# cheetah_driver_2.net
KiCad netlist of a schematic drawn in EAGLE
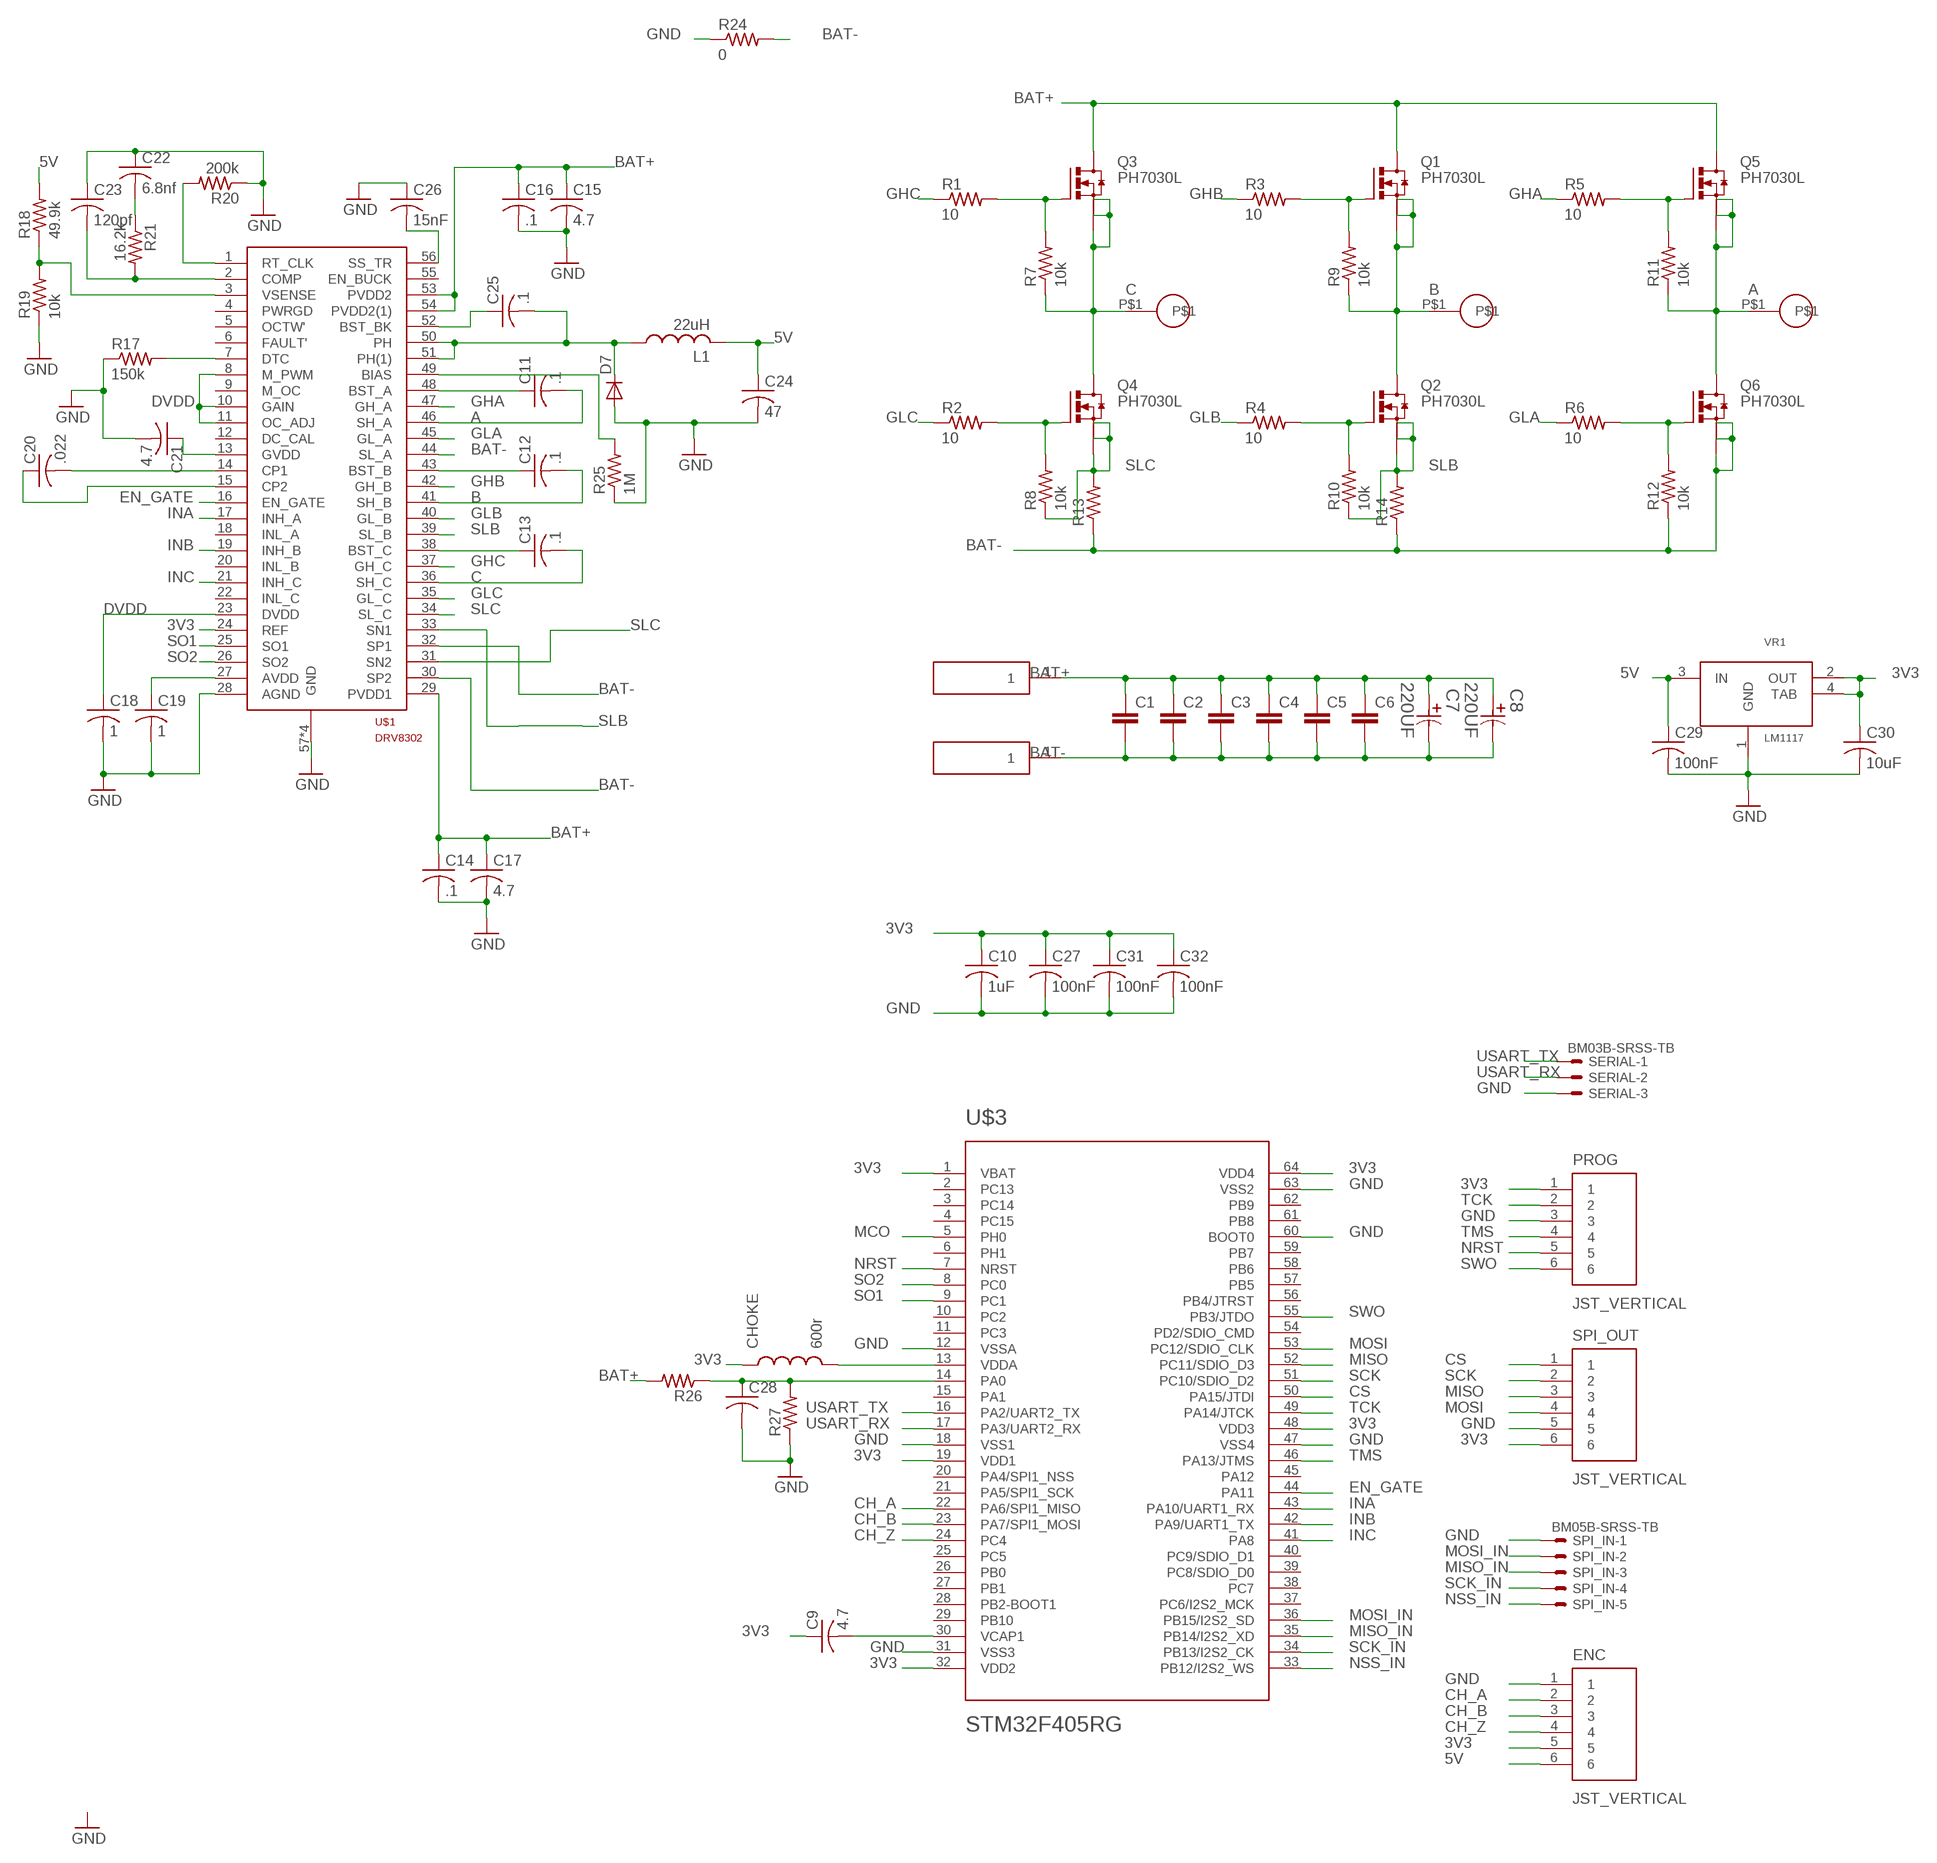
[diagram p0: schematic, sheet 1]

(export (version "E")
  (design (tool "Eeschema 10.0.6"))
  (components
    (comp (ref "C1")
      (value "C-EUC0805")
      (footprint "eagle-import:C0805")
      (libsource (lib "eagle-import") (part "C-EUC0805"))
    )
    (comp (ref "C2")
      (value "C-EUC0805")
      (footprint "eagle-import:C0805")
      (libsource (lib "eagle-import") (part "C-EUC0805"))
    )
    (comp (ref "C3")
      (value "C-EUC0805")
      (footprint "eagle-import:C0805")
      (libsource (lib "eagle-import") (part "C-EUC0805"))
    )
    (comp (ref "C4")
      (value "C-EUC0805")
      (footprint "eagle-import:C0805")
      (libsource (lib "eagle-import") (part "C-EUC0805"))
    )
    (comp (ref "C5")
      (value "C-EUC0805")
      (footprint "eagle-import:C0805")
      (libsource (lib "eagle-import") (part "C-EUC0805"))
    )
    (comp (ref "C6")
      (value "C-EUC0805")
      (footprint "eagle-import:C0805")
      (libsource (lib "eagle-import") (part "C-EUC0805"))
    )
    (comp (ref "C7")
      (value "220UF")
      (footprint "eagle-import:CAPAE830X1050N")
      (fields (field (name "MPN") "EEE-TK1A221P") (field (name "TOLERANCE") "±20 %"))
      (libsource (lib "eagle-import") (part "EEE--CASE-FTK1A221P"))
    )
    (comp (ref "C8")
      (value "220UF")
      (footprint "eagle-import:CAPAE830X1050N")
      (fields (field (name "MPN") "EEE-TK1A221P") (field (name "TOLERANCE") "±20 %"))
      (libsource (lib "eagle-import") (part "EEE--CASE-FTK1A221P"))
    )
    (comp (ref "C9")
      (value "4.7")
      (footprint "eagle-import:C0603")
      (libsource (lib "eagle-import") (part "C-USC0603"))
    )
    (comp (ref "C10")
      (value "1uF")
      (footprint "eagle-import:C0603")
      (libsource (lib "eagle-import") (part "C-USC0603"))
    )
    (comp (ref "C11")
      (value ".1")
      (footprint "eagle-import:C0603")
      (libsource (lib "eagle-import") (part "C-USC0603"))
    )
    (comp (ref "C12")
      (value ".1")
      (footprint "eagle-import:C0603")
      (libsource (lib "eagle-import") (part "C-USC0603"))
    )
    (comp (ref "C13")
      (value ".1")
      (footprint "eagle-import:C0603")
      (libsource (lib "eagle-import") (part "C-USC0603"))
    )
    (comp (ref "C14")
      (value ".1")
      (footprint "eagle-import:C0603")
      (libsource (lib "eagle-import") (part "C-USC0603"))
    )
    (comp (ref "C15")
      (value "4.7")
      (footprint "eagle-import:C0805")
      (libsource (lib "eagle-import") (part "C-USC0805"))
    )
    (comp (ref "C16")
      (value ".1")
      (footprint "eagle-import:C0603")
      (libsource (lib "eagle-import") (part "C-USC0603"))
    )
    (comp (ref "C17")
      (value "4.7")
      (footprint "eagle-import:C0805")
      (libsource (lib "eagle-import") (part "C-USC0805"))
    )
    (comp (ref "C18")
      (value "1")
      (footprint "eagle-import:C0603")
      (libsource (lib "eagle-import") (part "C-USC0603"))
    )
    (comp (ref "C19")
      (value "1")
      (footprint "eagle-import:C0603")
      (libsource (lib "eagle-import") (part "C-USC0603"))
    )
    (comp (ref "C20")
      (value ".022")
      (footprint "eagle-import:C0603")
      (libsource (lib "eagle-import") (part "C-USC0603"))
    )
    (comp (ref "C21")
      (value "4.7")
      (footprint "eagle-import:C0805")
      (libsource (lib "eagle-import") (part "C-USC0805"))
    )
    (comp (ref "C22")
      (value "6.8nf")
      (footprint "eagle-import:C0603")
      (libsource (lib "eagle-import") (part "C-USC0603"))
    )
    (comp (ref "C23")
      (value "120pf")
      (footprint "eagle-import:C0603")
      (libsource (lib "eagle-import") (part "C-USC0603"))
    )
    (comp (ref "C24")
      (value "47")
      (footprint "eagle-import:C1210")
      (libsource (lib "eagle-import") (part "C-USC1210"))
    )
    (comp (ref "C25")
      (value ".1")
      (footprint "eagle-import:C0603")
      (libsource (lib "eagle-import") (part "C-USC0603"))
    )
    (comp (ref "C26")
      (value "15nF")
      (footprint "eagle-import:C0603")
      (libsource (lib "eagle-import") (part "C-USC0603"))
    )
    (comp (ref "C27")
      (value "100nF")
      (footprint "eagle-import:C0603")
      (libsource (lib "eagle-import") (part "C-USC0603"))
    )
    (comp (ref "C28")
      (value "C-USC0603")
      (footprint "eagle-import:C0603")
      (libsource (lib "eagle-import") (part "C-USC0603"))
    )
    (comp (ref "C29")
      (value "100nF")
      (footprint "eagle-import:C0603")
      (libsource (lib "eagle-import") (part "C-USC0603"))
    )
    (comp (ref "C30")
      (value "10uF")
      (footprint "eagle-import:C0603")
      (libsource (lib "eagle-import") (part "C-USC0603"))
    )
    (comp (ref "C31")
      (value "100nF")
      (footprint "eagle-import:C0603")
      (libsource (lib "eagle-import") (part "C-USC0603"))
    )
    (comp (ref "C32")
      (value "100nF")
      (footprint "eagle-import:C0603")
      (libsource (lib "eagle-import") (part "C-USC0603"))
    )
    (comp (ref "CHOKE")
      (value "600r")
      (footprint "eagle-import:0603")
      (libsource (lib "eagle-import") (part "INDUCTOR0603"))
    )
    (comp (ref "D7")
      (value "DIODE-DO-214AC")
      (footprint "eagle-import:DO-214AC")
      (libsource (lib "eagle-import") (part "DIODE-DO-214AC"))
    )
    (comp (ref "ENC")
      (value "JST_VERTICAL")
      (footprint "eagle-import:JST-6-SMD-VERT-1.0MM")
      (libsource (lib "eagle-import") (part "JST_VERTICAL"))
    )
    (comp (ref "J4")
      (value "0.125_PAD")
      (footprint "eagle-import:0.125_PAD")
      (libsource (lib "eagle-import") (part "0.125_PAD"))
    )
    (comp (ref "J5")
      (value "0.125_PAD")
      (footprint "eagle-import:0.125_PAD")
      (libsource (lib "eagle-import") (part "0.125_PAD"))
    )
    (comp (ref "L1")
      (value "22uH")
      (footprint "eagle-import:L4532P")
      (libsource (lib "eagle-import") (part "L-USL4532P"))
    )
    (comp (ref "PROG")
      (value "JST_VERTICAL")
      (footprint "eagle-import:JST-6-SMD-VERT-1.0MM")
      (libsource (lib "eagle-import") (part "JST_VERTICAL"))
    )
    (comp (ref "Q1")
      (value "PH7030L")
      (footprint "eagle-import:SOT669")
      (libsource (lib "eagle-import") (part "PH7030L"))
    )
    (comp (ref "Q2")
      (value "PH7030L")
      (footprint "eagle-import:SOT669")
      (libsource (lib "eagle-import") (part "PH7030L"))
    )
    (comp (ref "Q3")
      (value "PH7030L")
      (footprint "eagle-import:SOT669")
      (libsource (lib "eagle-import") (part "PH7030L"))
    )
    (comp (ref "Q4")
      (value "PH7030L")
      (footprint "eagle-import:SOT669")
      (libsource (lib "eagle-import") (part "PH7030L"))
    )
    (comp (ref "Q5")
      (value "PH7030L")
      (footprint "eagle-import:SOT669")
      (libsource (lib "eagle-import") (part "PH7030L"))
    )
    (comp (ref "Q6")
      (value "PH7030L")
      (footprint "eagle-import:SOT669")
      (libsource (lib "eagle-import") (part "PH7030L"))
    )
    (comp (ref "R1")
      (value "10")
      (footprint "eagle-import:R0603")
      (libsource (lib "eagle-import") (part "R-US_R0603"))
    )
    (comp (ref "R2")
      (value "10")
      (footprint "eagle-import:R0603")
      (libsource (lib "eagle-import") (part "R-US_R0603"))
    )
    (comp (ref "R3")
      (value "10")
      (footprint "eagle-import:R0603")
      (libsource (lib "eagle-import") (part "R-US_R0603"))
    )
    (comp (ref "R4")
      (value "10")
      (footprint "eagle-import:R0603")
      (libsource (lib "eagle-import") (part "R-US_R0603"))
    )
    (comp (ref "R5")
      (value "10")
      (footprint "eagle-import:R0603")
      (libsource (lib "eagle-import") (part "R-US_R0603"))
    )
    (comp (ref "R6")
      (value "10")
      (footprint "eagle-import:R0603")
      (libsource (lib "eagle-import") (part "R-US_R0603"))
    )
    (comp (ref "R7")
      (value "10k")
      (footprint "eagle-import:R0603")
      (libsource (lib "eagle-import") (part "R-US_R0603"))
    )
    (comp (ref "R8")
      (value "10k")
      (footprint "eagle-import:R0603")
      (libsource (lib "eagle-import") (part "R-US_R0603"))
    )
    (comp (ref "R9")
      (value "10k")
      (footprint "eagle-import:R0603")
      (libsource (lib "eagle-import") (part "R-US_R0603"))
    )
    (comp (ref "R10")
      (value "10k")
      (footprint "eagle-import:R0603")
      (libsource (lib "eagle-import") (part "R-US_R0603"))
    )
    (comp (ref "R11")
      (value "10k")
      (footprint "eagle-import:R0603")
      (libsource (lib "eagle-import") (part "R-US_R0603"))
    )
    (comp (ref "R12")
      (value "10k")
      (footprint "eagle-import:R0603")
      (libsource (lib "eagle-import") (part "R-US_R0603"))
    )
    (comp (ref "R13")
      (value "R-US_R1210")
      (footprint "eagle-import:R1210")
      (libsource (lib "eagle-import") (part "R-US_R1210"))
    )
    (comp (ref "R14")
      (value "R-US_R1210")
      (footprint "eagle-import:R1210")
      (libsource (lib "eagle-import") (part "R-US_R1210"))
    )
    (comp (ref "R17")
      (value "150k")
      (footprint "eagle-import:R0603")
      (libsource (lib "eagle-import") (part "R-US_R0603"))
    )
    (comp (ref "R18")
      (value "49.9k")
      (footprint "eagle-import:R0603")
      (libsource (lib "eagle-import") (part "R-US_R0603"))
    )
    (comp (ref "R19")
      (value "10k")
      (footprint "eagle-import:R0603")
      (libsource (lib "eagle-import") (part "R-US_R0603"))
    )
    (comp (ref "R20")
      (value "200k")
      (footprint "eagle-import:R0603")
      (libsource (lib "eagle-import") (part "R-US_R0603"))
    )
    (comp (ref "R21")
      (value "16.2k")
      (footprint "eagle-import:R0603")
      (libsource (lib "eagle-import") (part "R-US_R0603"))
    )
    (comp (ref "R24")
      (value "0")
      (footprint "eagle-import:R0603")
      (libsource (lib "eagle-import") (part "R-US_R0603"))
    )
    (comp (ref "R25")
      (value "1M")
      (footprint "eagle-import:R0603")
      (libsource (lib "eagle-import") (part "R-US_R0603"))
    )
    (comp (ref "R26")
      (value "R-US_R0603")
      (footprint "eagle-import:R0603")
      (libsource (lib "eagle-import") (part "R-US_R0603"))
    )
    (comp (ref "R27")
      (value "R-US_R0603")
      (footprint "eagle-import:R0603")
      (libsource (lib "eagle-import") (part "R-US_R0603"))
    )
    (comp (ref "SERIAL")
      (value "BM03B-SRSS-TB")
      (footprint "eagle-import:BM03B-SRSS-TB")
      (libsource (lib "eagle-import") (part "?M03B-SRSS-TBB"))
    )
    (comp (ref "SPI_IN")
      (value "BM05B-SRSS-TB")
      (footprint "eagle-import:BM05B-SRSS-TB")
      (libsource (lib "eagle-import") (part "?M05B-SRSS-TBB"))
    )
    (comp (ref "SPI_OUT")
      (value "JST_VERTICAL")
      (footprint "eagle-import:JST-6-SMD-VERT-1.0MM")
      (libsource (lib "eagle-import") (part "JST_VERTICAL"))
    )
    (comp (ref "U$1")
      (value "DRV8302")
      (footprint "eagle-import:HTSSOP56")
      (libsource (lib "eagle-import") (part "DRV8302"))
    )
    (comp (ref "U$2")
      (value "18_AWG_PAD")
      (footprint "eagle-import:18_AWG_PAD")
      (libsource (lib "eagle-import") (part "18_AWG_PAD"))
    )
    (comp (ref "U$3")
      (value "STM32F405RG")
      (footprint "eagle-import:TQFP64")
      (libsource (lib "eagle-import") (part "STM32F405RG"))
    )
    (comp (ref "U$4")
      (value "18_AWG_PAD")
      (footprint "eagle-import:18_AWG_PAD")
      (libsource (lib "eagle-import") (part "18_AWG_PAD"))
    )
    (comp (ref "U$5")
      (value "18_AWG_PAD")
      (footprint "eagle-import:18_AWG_PAD")
      (libsource (lib "eagle-import") (part "18_AWG_PAD"))
    )
    (comp (ref "VR1")
      (value "LM1117")
      (footprint "eagle-import:SOT-223")
      (libsource (lib "eagle-import") (part "LM1117"))
    )
  )
  (nets
    (net (code "1") (name "/3V3") (class "Default")
      (node (ref "C10") (pin "1") (pinfunction "1_1") (pintype "passive"))
      (node (ref "C27") (pin "1") (pinfunction "1_1") (pintype "passive"))
      (node (ref "C30") (pin "1") (pinfunction "1_1") (pintype "passive"))
      (node (ref "C31") (pin "1") (pinfunction "1_1") (pintype "passive"))
      (node (ref "C32") (pin "1") (pinfunction "1_1") (pintype "passive"))
      (node (ref "C9") (pin "1") (pinfunction "1_1") (pintype "passive"))
      (node (ref "CHOKE") (pin "1") (pinfunction "1_1") (pintype "passive"))
      (node (ref "ENC") (pin "5") (pinfunction "5_5") (pintype "bidirectional"))
      (node (ref "PROG") (pin "1") (pinfunction "1_1") (pintype "bidirectional"))
      (node (ref "SPI_OUT") (pin "6") (pinfunction "6_6") (pintype "bidirectional"))
      (node (ref "U$1") (pin "24") (pinfunction "REF_24") (pintype "bidirectional"))
      (node (ref "U$3") (pin "1") (pinfunction "VBAT_1") (pintype "bidirectional"))
      (node (ref "U$3") (pin "19") (pinfunction "VDD1_19") (pintype "bidirectional"))
      (node (ref "U$3") (pin "32") (pinfunction "VDD2_32") (pintype "bidirectional"))
      (node (ref "U$3") (pin "48") (pinfunction "VDD3_48") (pintype "bidirectional"))
      (node (ref "U$3") (pin "64") (pinfunction "VDD4_64") (pintype "bidirectional"))
      (node (ref "VR1") (pin "2") (pinfunction "OUT_2") (pintype "bidirectional"))
      (node (ref "VR1") (pin "4") (pinfunction "TAB_4") (pintype "bidirectional"))
    )
    (net (code "2") (name "/5V") (class "Default")
      (node (ref "C24") (pin "1") (pinfunction "1_1") (pintype "passive"))
      (node (ref "C29") (pin "1") (pinfunction "1_1") (pintype "passive"))
      (node (ref "ENC") (pin "6") (pinfunction "6_6") (pintype "bidirectional"))
      (node (ref "L1") (pin "2") (pinfunction "2_2") (pintype "passive"))
      (node (ref "R18") (pin "2") (pinfunction "2_2") (pintype "passive"))
      (node (ref "VR1") (pin "3") (pinfunction "IN_3") (pintype "bidirectional"))
    )
    (net (code "3") (name "/A") (class "Default")
      (node (ref "C11") (pin "2") (pinfunction "2_2") (pintype "passive"))
      (node (ref "Q5") (pin "1") (pinfunction "S_1") (pintype "passive"))
      (node (ref "Q5") (pin "2") (pinfunction "S_2") (pintype "passive"))
      (node (ref "Q5") (pin "3") (pinfunction "S_3") (pintype "passive"))
      (node (ref "Q6") (pin "MB") (pinfunction "D_MB") (pintype "passive"))
      (node (ref "R11") (pin "1") (pinfunction "1_1") (pintype "passive"))
      (node (ref "U$1") (pin "46") (pinfunction "SH_A_46") (pintype "bidirectional"))
      (node (ref "U$5") (pin "P$1") (pinfunction "P$1_P$1") (pintype "bidirectional"))
    )
    (net (code "4") (name "/B") (class "Default")
      (node (ref "C12") (pin "2") (pinfunction "2_2") (pintype "passive"))
      (node (ref "Q1") (pin "1") (pinfunction "S_1") (pintype "passive"))
      (node (ref "Q1") (pin "2") (pinfunction "S_2") (pintype "passive"))
      (node (ref "Q1") (pin "3") (pinfunction "S_3") (pintype "passive"))
      (node (ref "Q2") (pin "MB") (pinfunction "D_MB") (pintype "passive"))
      (node (ref "R9") (pin "1") (pinfunction "1_1") (pintype "passive"))
      (node (ref "U$1") (pin "41") (pinfunction "SH_B_41") (pintype "bidirectional"))
      (node (ref "U$4") (pin "P$1") (pinfunction "P$1_P$1") (pintype "bidirectional"))
    )
    (net (code "5") (name "/BAT+") (class "Default")
      (node (ref "C1") (pin "1") (pinfunction "1_1") (pintype "passive"))
      (node (ref "C14") (pin "1") (pinfunction "1_1") (pintype "passive"))
      (node (ref "C15") (pin "1") (pinfunction "1_1") (pintype "passive"))
      (node (ref "C16") (pin "1") (pinfunction "1_1") (pintype "passive"))
      (node (ref "C17") (pin "1") (pinfunction "1_1") (pintype "passive"))
      (node (ref "C2") (pin "1") (pinfunction "1_1") (pintype "passive"))
      (node (ref "C3") (pin "1") (pinfunction "1_1") (pintype "passive"))
      (node (ref "C4") (pin "1") (pinfunction "1_1") (pintype "passive"))
      (node (ref "C5") (pin "1") (pinfunction "1_1") (pintype "passive"))
      (node (ref "C6") (pin "1") (pinfunction "1_1") (pintype "passive"))
      (node (ref "C7") (pin "1") (pinfunction "1_1") (pintype "passive"))
      (node (ref "C8") (pin "1") (pinfunction "1_1") (pintype "passive"))
      (node (ref "J4") (pin "1") (pinfunction "1_1") (pintype "bidirectional"))
      (node (ref "Q1") (pin "MB") (pinfunction "D_MB") (pintype "passive"))
      (node (ref "Q3") (pin "MB") (pinfunction "D_MB") (pintype "passive"))
      (node (ref "Q5") (pin "MB") (pinfunction "D_MB") (pintype "passive"))
      (node (ref "R26") (pin "2") (pinfunction "2_2") (pintype "passive"))
      (node (ref "U$1") (pin "29") (pinfunction "PVDD1_29") (pintype "bidirectional"))
      (node (ref "U$1") (pin "53") (pinfunction "PVDD2_53") (pintype "bidirectional"))
      (node (ref "U$1") (pin "54") (pinfunction "PVDD2(1)_54") (pintype "bidirectional"))
    )
    (net (code "6") (name "/BAT-") (class "Default")
      (node (ref "C1") (pin "2") (pinfunction "2_2") (pintype "passive"))
      (node (ref "C2") (pin "2") (pinfunction "2_2") (pintype "passive"))
      (node (ref "C3") (pin "2") (pinfunction "2_2") (pintype "passive"))
      (node (ref "C4") (pin "2") (pinfunction "2_2") (pintype "passive"))
      (node (ref "C5") (pin "2") (pinfunction "2_2") (pintype "passive"))
      (node (ref "C6") (pin "2") (pinfunction "2_2") (pintype "passive"))
      (node (ref "C7") (pin "2") (pinfunction "2_2") (pintype "passive"))
      (node (ref "C8") (pin "2") (pinfunction "2_2") (pintype "passive"))
      (node (ref "J5") (pin "1") (pinfunction "1_1") (pintype "bidirectional"))
      (node (ref "Q6") (pin "1") (pinfunction "S_1") (pintype "passive"))
      (node (ref "Q6") (pin "2") (pinfunction "S_2") (pintype "passive"))
      (node (ref "Q6") (pin "3") (pinfunction "S_3") (pintype "passive"))
      (node (ref "R12") (pin "1") (pinfunction "1_1") (pintype "passive"))
      (node (ref "R13") (pin "1") (pinfunction "1_1") (pintype "passive"))
      (node (ref "R14") (pin "1") (pinfunction "1_1") (pintype "passive"))
      (node (ref "R24") (pin "2") (pinfunction "2_2") (pintype "passive"))
      (node (ref "U$1") (pin "30") (pinfunction "SP2_30") (pintype "bidirectional"))
      (node (ref "U$1") (pin "32") (pinfunction "SP1_32") (pintype "bidirectional"))
      (node (ref "U$1") (pin "44") (pinfunction "SL_A_44") (pintype "bidirectional"))
    )
    (net (code "7") (name "/C") (class "Default")
      (node (ref "C13") (pin "2") (pinfunction "2_2") (pintype "passive"))
      (node (ref "Q3") (pin "1") (pinfunction "S_1") (pintype "passive"))
      (node (ref "Q3") (pin "2") (pinfunction "S_2") (pintype "passive"))
      (node (ref "Q3") (pin "3") (pinfunction "S_3") (pintype "passive"))
      (node (ref "Q4") (pin "MB") (pinfunction "D_MB") (pintype "passive"))
      (node (ref "R7") (pin "1") (pinfunction "1_1") (pintype "passive"))
      (node (ref "U$1") (pin "36") (pinfunction "SH_C_36") (pintype "bidirectional"))
      (node (ref "U$2") (pin "P$1") (pinfunction "P$1_P$1") (pintype "bidirectional"))
    )
    (net (code "8") (name "/CH_A") (class "Default")
      (node (ref "ENC") (pin "2") (pinfunction "2_2") (pintype "bidirectional"))
      (node (ref "U$3") (pin "22") (pinfunction "PA6/SPI1_MISO_22") (pintype "bidirectional"))
    )
    (net (code "9") (name "/CH_B") (class "Default")
      (node (ref "ENC") (pin "3") (pinfunction "3_3") (pintype "bidirectional"))
      (node (ref "U$3") (pin "23") (pinfunction "PA7/SPI1_MOSI_23") (pintype "bidirectional"))
    )
    (net (code "10") (name "/CH_Z") (class "Default")
      (node (ref "ENC") (pin "4") (pinfunction "4_4") (pintype "bidirectional"))
      (node (ref "U$3") (pin "24") (pinfunction "PC4_24") (pintype "bidirectional"))
    )
    (net (code "11") (name "/CS") (class "Default")
      (node (ref "SPI_OUT") (pin "1") (pinfunction "1_1") (pintype "bidirectional"))
      (node (ref "U$3") (pin "50") (pinfunction "PA15/JTDI_50") (pintype "bidirectional"))
    )
    (net (code "12") (name "/DVDD") (class "Default")
      (node (ref "C18") (pin "1") (pinfunction "1_1") (pintype "passive"))
      (node (ref "U$1") (pin "10") (pinfunction "GAIN_10") (pintype "bidirectional"))
      (node (ref "U$1") (pin "11") (pinfunction "OC_ADJ_11") (pintype "bidirectional"))
      (node (ref "U$1") (pin "23") (pinfunction "DVDD_23") (pintype "bidirectional"))
      (node (ref "U$1") (pin "8") (pinfunction "M_PWM_8") (pintype "bidirectional"))
    )
    (net (code "13") (name "/EN_GATE") (class "Default")
      (node (ref "U$1") (pin "16") (pinfunction "EN_GATE_16") (pintype "bidirectional"))
      (node (ref "U$3") (pin "44") (pinfunction "PA11_44") (pintype "bidirectional"))
    )
    (net (code "14") (name "/GHA") (class "Default")
      (node (ref "R5") (pin "1") (pinfunction "1_1") (pintype "passive"))
      (node (ref "U$1") (pin "47") (pinfunction "GH_A_47") (pintype "bidirectional"))
    )
    (net (code "15") (name "/GHB") (class "Default")
      (node (ref "R3") (pin "1") (pinfunction "1_1") (pintype "passive"))
      (node (ref "U$1") (pin "42") (pinfunction "GH_B_42") (pintype "bidirectional"))
    )
    (net (code "16") (name "/GHC") (class "Default")
      (node (ref "R1") (pin "1") (pinfunction "1_1") (pintype "passive"))
      (node (ref "U$1") (pin "37") (pinfunction "GH_C_37") (pintype "bidirectional"))
    )
    (net (code "17") (name "/GLA") (class "Default")
      (node (ref "R6") (pin "1") (pinfunction "1_1") (pintype "passive"))
      (node (ref "U$1") (pin "45") (pinfunction "GL_A_45") (pintype "bidirectional"))
    )
    (net (code "18") (name "/GLB") (class "Default")
      (node (ref "R4") (pin "1") (pinfunction "1_1") (pintype "passive"))
      (node (ref "U$1") (pin "40") (pinfunction "GL_B_40") (pintype "bidirectional"))
    )
    (net (code "19") (name "/GLC") (class "Default")
      (node (ref "R2") (pin "1") (pinfunction "1_1") (pintype "passive"))
      (node (ref "U$1") (pin "35") (pinfunction "GL_C_35") (pintype "bidirectional"))
    )
    (net (code "20") (name "/INA") (class "Default")
      (node (ref "U$1") (pin "17") (pinfunction "INH_A_17") (pintype "bidirectional"))
      (node (ref "U$3") (pin "43") (pinfunction "PA10/UART1_RX_43") (pintype "bidirectional"))
    )
    (net (code "21") (name "/INB") (class "Default")
      (node (ref "U$1") (pin "19") (pinfunction "INH_B_19") (pintype "bidirectional"))
      (node (ref "U$3") (pin "42") (pinfunction "PA9/UART1_TX_42") (pintype "bidirectional"))
    )
    (net (code "22") (name "/INC") (class "Default")
      (node (ref "U$1") (pin "21") (pinfunction "INH_C_21") (pintype "bidirectional"))
      (node (ref "U$3") (pin "41") (pinfunction "PA8_41") (pintype "bidirectional"))
    )
    (net (code "23") (name "/MCO") (class "Default")
      (node (ref "U$3") (pin "5") (pinfunction "PH0_5") (pintype "bidirectional"))
    )
    (net (code "24") (name "/MISO") (class "Default")
      (node (ref "SPI_OUT") (pin "3") (pinfunction "3_3") (pintype "bidirectional"))
      (node (ref "U$3") (pin "52") (pinfunction "PC11/SDIO_D3_52") (pintype "bidirectional"))
    )
    (net (code "25") (name "/MISO_IN") (class "Default")
      (node (ref "SPI_IN") (pin "3") (pinfunction "S_3") (pintype "passive"))
      (node (ref "U$3") (pin "35") (pinfunction "PB14/I2S2_XD_35") (pintype "bidirectional"))
    )
    (net (code "26") (name "/MOSI") (class "Default")
      (node (ref "SPI_OUT") (pin "4") (pinfunction "4_4") (pintype "bidirectional"))
      (node (ref "U$3") (pin "53") (pinfunction "PC12/SDIO_CLK_53") (pintype "bidirectional"))
    )
    (net (code "27") (name "/MOSI_IN") (class "Default")
      (node (ref "SPI_IN") (pin "2") (pinfunction "S_2") (pintype "passive"))
      (node (ref "U$3") (pin "36") (pinfunction "PB15/I2S2_SD_36") (pintype "bidirectional"))
    )
    (net (code "28") (name "/NRST") (class "Default")
      (node (ref "PROG") (pin "5") (pinfunction "5_5") (pintype "bidirectional"))
      (node (ref "U$3") (pin "7") (pinfunction "NRST_7") (pintype "bidirectional"))
    )
    (net (code "29") (name "/NSS_IN") (class "Default")
      (node (ref "SPI_IN") (pin "5") (pinfunction "S_5") (pintype "passive"))
      (node (ref "U$3") (pin "33") (pinfunction "PB12/I2S2_WS_33") (pintype "bidirectional"))
    )
    (net (code "30") (name "/SCK") (class "Default")
      (node (ref "SPI_OUT") (pin "2") (pinfunction "2_2") (pintype "bidirectional"))
      (node (ref "U$3") (pin "51") (pinfunction "PC10/SDIO_D2_51") (pintype "bidirectional"))
    )
    (net (code "31") (name "/SCK_IN") (class "Default")
      (node (ref "SPI_IN") (pin "4") (pinfunction "S_4") (pintype "passive"))
      (node (ref "U$3") (pin "34") (pinfunction "PB13/I2S2_CK_34") (pintype "bidirectional"))
    )
    (net (code "32") (name "/SLB") (class "Default")
      (node (ref "Q2") (pin "1") (pinfunction "S_1") (pintype "passive"))
      (node (ref "Q2") (pin "2") (pinfunction "S_2") (pintype "passive"))
      (node (ref "Q2") (pin "3") (pinfunction "S_3") (pintype "passive"))
      (node (ref "R10") (pin "1") (pinfunction "1_1") (pintype "passive"))
      (node (ref "R14") (pin "2") (pinfunction "2_2") (pintype "passive"))
      (node (ref "U$1") (pin "33") (pinfunction "SN1_33") (pintype "bidirectional"))
      (node (ref "U$1") (pin "39") (pinfunction "SL_B_39") (pintype "bidirectional"))
    )
    (net (code "33") (name "/SLC") (class "Default")
      (node (ref "Q4") (pin "1") (pinfunction "S_1") (pintype "passive"))
      (node (ref "Q4") (pin "2") (pinfunction "S_2") (pintype "passive"))
      (node (ref "Q4") (pin "3") (pinfunction "S_3") (pintype "passive"))
      (node (ref "R13") (pin "2") (pinfunction "2_2") (pintype "passive"))
      (node (ref "R8") (pin "1") (pinfunction "1_1") (pintype "passive"))
      (node (ref "U$1") (pin "31") (pinfunction "SN2_31") (pintype "bidirectional"))
      (node (ref "U$1") (pin "34") (pinfunction "SL_C_34") (pintype "bidirectional"))
    )
    (net (code "34") (name "/SO1") (class "Default")
      (node (ref "U$1") (pin "25") (pinfunction "SO1_25") (pintype "bidirectional"))
      (node (ref "U$3") (pin "9") (pinfunction "PC1_9") (pintype "bidirectional"))
    )
    (net (code "35") (name "/SO2") (class "Default")
      (node (ref "U$1") (pin "26") (pinfunction "SO2_26") (pintype "bidirectional"))
      (node (ref "U$3") (pin "8") (pinfunction "PC0_8") (pintype "bidirectional"))
    )
    (net (code "36") (name "/SWO") (class "Default")
      (node (ref "PROG") (pin "6") (pinfunction "6_6") (pintype "bidirectional"))
      (node (ref "U$3") (pin "55") (pinfunction "PB3/JTDO_55") (pintype "bidirectional"))
    )
    (net (code "37") (name "/TCK") (class "Default")
      (node (ref "PROG") (pin "2") (pinfunction "2_2") (pintype "bidirectional"))
      (node (ref "U$3") (pin "49") (pinfunction "PA14/JTCK_49") (pintype "bidirectional"))
    )
    (net (code "38") (name "/TMS") (class "Default")
      (node (ref "PROG") (pin "4") (pinfunction "4_4") (pintype "bidirectional"))
      (node (ref "U$3") (pin "46") (pinfunction "PA13/JTMS_46") (pintype "bidirectional"))
    )
    (net (code "39") (name "/USART_RX") (class "Default")
      (node (ref "SERIAL") (pin "2") (pinfunction "S_2") (pintype "passive"))
      (node (ref "U$3") (pin "17") (pinfunction "PA3/UART2_RX_17") (pintype "bidirectional"))
    )
    (net (code "40") (name "/USART_TX") (class "Default")
      (node (ref "SERIAL") (pin "1") (pinfunction "S_1") (pintype "passive"))
      (node (ref "U$3") (pin "16") (pinfunction "PA2/UART2_TX_16") (pintype "bidirectional"))
    )
    (net (code "41") (name "GND") (class "Default")
      (node (ref "C10") (pin "2") (pinfunction "2_2") (pintype "passive"))
      (node (ref "C14") (pin "2") (pinfunction "2_2") (pintype "passive"))
      (node (ref "C15") (pin "2") (pinfunction "2_2") (pintype "passive"))
      (node (ref "C16") (pin "2") (pinfunction "2_2") (pintype "passive"))
      (node (ref "C17") (pin "2") (pinfunction "2_2") (pintype "passive"))
      (node (ref "C18") (pin "2") (pinfunction "2_2") (pintype "passive"))
      (node (ref "C19") (pin "2") (pinfunction "2_2") (pintype "passive"))
      (node (ref "C21") (pin "2") (pinfunction "2_2") (pintype "passive"))
      (node (ref "C22") (pin "1") (pinfunction "1_1") (pintype "passive"))
      (node (ref "C23") (pin "1") (pinfunction "1_1") (pintype "passive"))
      (node (ref "C24") (pin "2") (pinfunction "2_2") (pintype "passive"))
      (node (ref "C26") (pin "1") (pinfunction "1_1") (pintype "passive"))
      (node (ref "C27") (pin "2") (pinfunction "2_2") (pintype "passive"))
      (node (ref "C28") (pin "2") (pinfunction "2_2") (pintype "passive"))
      (node (ref "C29") (pin "2") (pinfunction "2_2") (pintype "passive"))
      (node (ref "C30") (pin "2") (pinfunction "2_2") (pintype "passive"))
      (node (ref "C31") (pin "2") (pinfunction "2_2") (pintype "passive"))
      (node (ref "C32") (pin "2") (pinfunction "2_2") (pintype "passive"))
      (node (ref "D7") (pin "A") (pinfunction "A_A") (pintype "passive"))
      (node (ref "ENC") (pin "1") (pinfunction "1_1") (pintype "bidirectional"))
      (node (ref "PROG") (pin "3") (pinfunction "3_3") (pintype "bidirectional"))
      (node (ref "R17") (pin "1") (pinfunction "1_1") (pintype "passive"))
      (node (ref "R19") (pin "1") (pinfunction "1_1") (pintype "passive"))
      (node (ref "R20") (pin "1") (pinfunction "1_1") (pintype "passive"))
      (node (ref "R24") (pin "1") (pinfunction "1_1") (pintype "passive"))
      (node (ref "R25") (pin "1") (pinfunction "1_1") (pintype "passive"))
      (node (ref "R27") (pin "1") (pinfunction "1_1") (pintype "passive"))
      (node (ref "SERIAL") (pin "3") (pinfunction "S_3") (pintype "passive"))
      (node (ref "SPI_IN") (pin "1") (pinfunction "S_1") (pintype "passive"))
      (node (ref "SPI_OUT") (pin "5") (pinfunction "5_5") (pintype "bidirectional"))
      (node (ref "U$1") (pin "28") (pinfunction "AGND_28") (pintype "bidirectional"))
      (node (ref "U$1") (pin "57") (pinfunction "GND_57") (pintype "bidirectional"))
      (node (ref "U$1") (pin "P$1") (pinfunction "GND_P$1") (pintype "bidirectional"))
      (node (ref "U$1") (pin "P$2") (pinfunction "GND_P$2") (pintype "bidirectional"))
      (node (ref "U$1") (pin "P$3") (pinfunction "GND_P$3") (pintype "bidirectional"))
      (node (ref "U$3") (pin "12") (pinfunction "VSSA_12") (pintype "bidirectional"))
      (node (ref "U$3") (pin "18") (pinfunction "VSS1_18") (pintype "bidirectional"))
      (node (ref "U$3") (pin "31") (pinfunction "VSS3_31") (pintype "bidirectional"))
      (node (ref "U$3") (pin "47") (pinfunction "VSS4_47") (pintype "bidirectional"))
      (node (ref "U$3") (pin "60") (pinfunction "BOOT0_60") (pintype "bidirectional"))
      (node (ref "U$3") (pin "63") (pinfunction "VSS2_63") (pintype "bidirectional"))
      (node (ref "VR1") (pin "1") (pinfunction "GND_1") (pintype "bidirectional"))
    )
    (net (code "42") (name "Net-(C22-Pad2)") (class "Default")
      (node (ref "C22") (pin "2") (pinfunction "2_2") (pintype "passive"))
      (node (ref "R21") (pin "1") (pinfunction "1_1") (pintype "passive"))
    )
    (net (code "43") (name "Net-(Q1-G)") (class "Default")
      (node (ref "Q1") (pin "4") (pinfunction "G_4") (pintype "passive"))
      (node (ref "R3") (pin "2") (pinfunction "2_2") (pintype "passive"))
      (node (ref "R9") (pin "2") (pinfunction "2_2") (pintype "passive"))
    )
    (net (code "44") (name "Net-(Q2-G)") (class "Default")
      (node (ref "Q2") (pin "4") (pinfunction "G_4") (pintype "passive"))
      (node (ref "R10") (pin "2") (pinfunction "2_2") (pintype "passive"))
      (node (ref "R4") (pin "2") (pinfunction "2_2") (pintype "passive"))
    )
    (net (code "45") (name "Net-(Q3-G)") (class "Default")
      (node (ref "Q3") (pin "4") (pinfunction "G_4") (pintype "passive"))
      (node (ref "R1") (pin "2") (pinfunction "2_2") (pintype "passive"))
      (node (ref "R7") (pin "2") (pinfunction "2_2") (pintype "passive"))
    )
    (net (code "46") (name "Net-(Q4-G)") (class "Default")
      (node (ref "Q4") (pin "4") (pinfunction "G_4") (pintype "passive"))
      (node (ref "R2") (pin "2") (pinfunction "2_2") (pintype "passive"))
      (node (ref "R8") (pin "2") (pinfunction "2_2") (pintype "passive"))
    )
    (net (code "47") (name "Net-(Q5-G)") (class "Default")
      (node (ref "Q5") (pin "4") (pinfunction "G_4") (pintype "passive"))
      (node (ref "R11") (pin "2") (pinfunction "2_2") (pintype "passive"))
      (node (ref "R5") (pin "2") (pinfunction "2_2") (pintype "passive"))
    )
    (net (code "48") (name "Net-(Q6-G)") (class "Default")
      (node (ref "Q6") (pin "4") (pinfunction "G_4") (pintype "passive"))
      (node (ref "R12") (pin "2") (pinfunction "2_2") (pintype "passive"))
      (node (ref "R6") (pin "2") (pinfunction "2_2") (pintype "passive"))
    )
    (net (code "49") (name "Net-(U$1-AVDD)") (class "Default")
      (node (ref "C19") (pin "1") (pinfunction "1_1") (pintype "passive"))
      (node (ref "U$1") (pin "27") (pinfunction "AVDD_27") (pintype "bidirectional"))
    )
    (net (code "50") (name "Net-(U$1-BIAS)") (class "Default")
      (node (ref "R25") (pin "2") (pinfunction "2_2") (pintype "passive"))
      (node (ref "U$1") (pin "49") (pinfunction "BIAS_49") (pintype "bidirectional"))
    )
    (net (code "51") (name "Net-(U$1-BST_A)") (class "Default")
      (node (ref "C11") (pin "1") (pinfunction "1_1") (pintype "passive"))
      (node (ref "U$1") (pin "48") (pinfunction "BST_A_48") (pintype "bidirectional"))
    )
    (net (code "52") (name "Net-(U$1-BST_B)") (class "Default")
      (node (ref "C12") (pin "1") (pinfunction "1_1") (pintype "passive"))
      (node (ref "U$1") (pin "43") (pinfunction "BST_B_43") (pintype "bidirectional"))
    )
    (net (code "53") (name "Net-(U$1-BST_BK)") (class "Default")
      (node (ref "C25") (pin "1") (pinfunction "1_1") (pintype "passive"))
      (node (ref "U$1") (pin "52") (pinfunction "BST_BK_52") (pintype "bidirectional"))
    )
    (net (code "54") (name "Net-(U$1-BST_C)") (class "Default")
      (node (ref "C13") (pin "1") (pinfunction "1_1") (pintype "passive"))
      (node (ref "U$1") (pin "38") (pinfunction "BST_C_38") (pintype "bidirectional"))
    )
    (net (code "55") (name "Net-(U$1-COMP)") (class "Default")
      (node (ref "C23") (pin "2") (pinfunction "2_2") (pintype "passive"))
      (node (ref "R21") (pin "2") (pinfunction "2_2") (pintype "passive"))
      (node (ref "U$1") (pin "2") (pinfunction "COMP_2") (pintype "bidirectional"))
    )
    (net (code "56") (name "Net-(U$1-CP1)") (class "Default")
      (node (ref "C20") (pin "2") (pinfunction "2_2") (pintype "passive"))
      (node (ref "U$1") (pin "14") (pinfunction "CP1_14") (pintype "bidirectional"))
    )
    (net (code "57") (name "Net-(U$1-CP2)") (class "Default")
      (node (ref "C20") (pin "1") (pinfunction "1_1") (pintype "passive"))
      (node (ref "U$1") (pin "15") (pinfunction "CP2_15") (pintype "bidirectional"))
    )
    (net (code "58") (name "Net-(U$1-DTC)") (class "Default")
      (node (ref "R17") (pin "2") (pinfunction "2_2") (pintype "passive"))
      (node (ref "U$1") (pin "7") (pinfunction "DTC_7") (pintype "bidirectional"))
    )
    (net (code "59") (name "Net-(U$1-GVDD)") (class "Default")
      (node (ref "C21") (pin "1") (pinfunction "1_1") (pintype "passive"))
      (node (ref "U$1") (pin "13") (pinfunction "GVDD_13") (pintype "bidirectional"))
    )
    (net (code "60") (name "Net-(U$1-PH(1))") (class "Default")
      (node (ref "C25") (pin "2") (pinfunction "2_2") (pintype "passive"))
      (node (ref "D7") (pin "C") (pinfunction "C_C") (pintype "passive"))
      (node (ref "L1") (pin "1") (pinfunction "1_1") (pintype "passive"))
      (node (ref "U$1") (pin "50") (pinfunction "PH_50") (pintype "bidirectional"))
      (node (ref "U$1") (pin "51") (pinfunction "PH(1)_51") (pintype "bidirectional"))
    )
    (net (code "61") (name "Net-(U$1-RT_CLK)") (class "Default")
      (node (ref "R20") (pin "2") (pinfunction "2_2") (pintype "passive"))
      (node (ref "U$1") (pin "1") (pinfunction "RT_CLK_1") (pintype "bidirectional"))
    )
    (net (code "62") (name "Net-(U$1-SS_TR)") (class "Default")
      (node (ref "C26") (pin "2") (pinfunction "2_2") (pintype "passive"))
      (node (ref "U$1") (pin "56") (pinfunction "SS_TR_56") (pintype "bidirectional"))
    )
    (net (code "63") (name "Net-(U$1-VSENSE)") (class "Default")
      (node (ref "R18") (pin "1") (pinfunction "1_1") (pintype "passive"))
      (node (ref "R19") (pin "2") (pinfunction "2_2") (pintype "passive"))
      (node (ref "U$1") (pin "3") (pinfunction "VSENSE_3") (pintype "bidirectional"))
    )
    (net (code "64") (name "Net-(U$3-PA0)") (class "Default")
      (node (ref "C28") (pin "1") (pinfunction "1_1") (pintype "passive"))
      (node (ref "R26") (pin "1") (pinfunction "1_1") (pintype "passive"))
      (node (ref "R27") (pin "2") (pinfunction "2_2") (pintype "passive"))
      (node (ref "U$3") (pin "14") (pinfunction "PA0_14") (pintype "bidirectional"))
    )
    (net (code "65") (name "Net-(U$3-VCAP1)") (class "Default")
      (node (ref "C9") (pin "2") (pinfunction "2_2") (pintype "passive"))
      (node (ref "U$3") (pin "30") (pinfunction "VCAP1_30") (pintype "bidirectional"))
    )
    (net (code "66") (name "Net-(U$3-VDDA)") (class "Default")
      (node (ref "CHOKE") (pin "2") (pinfunction "2_2") (pintype "passive"))
      (node (ref "U$3") (pin "13") (pinfunction "VDDA_13") (pintype "bidirectional"))
    )
    (net (code "67") (name "unconnected-(U$1-DC_CAL-Pad12)") (class "Default")
      (node (ref "U$1") (pin "12") (pinfunction "DC_CAL_12") (pintype "bidirectional"))
    )
    (net (code "68") (name "unconnected-(U$1-EN_BUCK-Pad55)") (class "Default")
      (node (ref "U$1") (pin "55") (pinfunction "EN_BUCK_55") (pintype "bidirectional"))
    )
    (net (code "69") (name "unconnected-(U$1-FAULT'-Pad6)") (class "Default")
      (node (ref "U$1") (pin "6") (pinfunction "FAULT'_6") (pintype "bidirectional"))
    )
    (net (code "70") (name "unconnected-(U$1-INL_A-Pad18)") (class "Default")
      (node (ref "U$1") (pin "18") (pinfunction "INL_A_18") (pintype "bidirectional"))
    )
    (net (code "71") (name "unconnected-(U$1-INL_B-Pad20)") (class "Default")
      (node (ref "U$1") (pin "20") (pinfunction "INL_B_20") (pintype "bidirectional"))
    )
    (net (code "72") (name "unconnected-(U$1-INL_C-Pad22)") (class "Default")
      (node (ref "U$1") (pin "22") (pinfunction "INL_C_22") (pintype "bidirectional"))
    )
    (net (code "73") (name "unconnected-(U$1-M_OC-Pad9)") (class "Default")
      (node (ref "U$1") (pin "9") (pinfunction "M_OC_9") (pintype "bidirectional"))
    )
    (net (code "74") (name "unconnected-(U$1-OCTW'-Pad5)") (class "Default")
      (node (ref "U$1") (pin "5") (pinfunction "OCTW'_5") (pintype "bidirectional"))
    )
    (net (code "75") (name "unconnected-(U$1-PWRGD-Pad4)") (class "Default")
      (node (ref "U$1") (pin "4") (pinfunction "PWRGD_4") (pintype "bidirectional"))
    )
    (net (code "76") (name "unconnected-(U$3-PA1-Pad15)") (class "Default")
      (node (ref "U$3") (pin "15") (pinfunction "PA1_15") (pintype "bidirectional"))
    )
    (net (code "77") (name "unconnected-(U$3-PA4{slash}SPI1_NSS-Pad20)") (class "Default")
      (node (ref "U$3") (pin "20") (pinfunction "PA4/SPI1_NSS_20") (pintype "bidirectional"))
    )
    (net (code "78") (name "unconnected-(U$3-PA5{slash}SPI1_SCK-Pad21)") (class "Default")
      (node (ref "U$3") (pin "21") (pinfunction "PA5/SPI1_SCK_21") (pintype "bidirectional"))
    )
    (net (code "79") (name "unconnected-(U$3-PA12-Pad45)") (class "Default")
      (node (ref "U$3") (pin "45") (pinfunction "PA12_45") (pintype "bidirectional"))
    )
    (net (code "80") (name "unconnected-(U$3-PB0-Pad26)") (class "Default")
      (node (ref "U$3") (pin "26") (pinfunction "PB0_26") (pintype "bidirectional"))
    )
    (net (code "81") (name "unconnected-(U$3-PB1-Pad27)") (class "Default")
      (node (ref "U$3") (pin "27") (pinfunction "PB1_27") (pintype "bidirectional"))
    )
    (net (code "82") (name "unconnected-(U$3-PB2-BOOT1-Pad28)") (class "Default")
      (node (ref "U$3") (pin "28") (pinfunction "PB2-BOOT1_28") (pintype "bidirectional"))
    )
    (net (code "83") (name "unconnected-(U$3-PB4{slash}JTRST-Pad56)") (class "Default")
      (node (ref "U$3") (pin "56") (pinfunction "PB4/JTRST_56") (pintype "bidirectional"))
    )
    (net (code "84") (name "unconnected-(U$3-PB5-Pad57)") (class "Default")
      (node (ref "U$3") (pin "57") (pinfunction "PB5_57") (pintype "bidirectional"))
    )
    (net (code "85") (name "unconnected-(U$3-PB6-Pad58)") (class "Default")
      (node (ref "U$3") (pin "58") (pinfunction "PB6_58") (pintype "bidirectional"))
    )
    (net (code "86") (name "unconnected-(U$3-PB7-Pad59)") (class "Default")
      (node (ref "U$3") (pin "59") (pinfunction "PB7_59") (pintype "bidirectional"))
    )
    (net (code "87") (name "unconnected-(U$3-PB8-Pad61)") (class "Default")
      (node (ref "U$3") (pin "61") (pinfunction "PB8_61") (pintype "bidirectional"))
    )
    (net (code "88") (name "unconnected-(U$3-PB9-Pad62)") (class "Default")
      (node (ref "U$3") (pin "62") (pinfunction "PB9_62") (pintype "bidirectional"))
    )
    (net (code "89") (name "unconnected-(U$3-PB10-Pad29)") (class "Default")
      (node (ref "U$3") (pin "29") (pinfunction "PB10_29") (pintype "bidirectional"))
    )
    (net (code "90") (name "unconnected-(U$3-PC2-Pad10)") (class "Default")
      (node (ref "U$3") (pin "10") (pinfunction "PC2_10") (pintype "bidirectional"))
    )
    (net (code "91") (name "unconnected-(U$3-PC3-Pad11)") (class "Default")
      (node (ref "U$3") (pin "11") (pinfunction "PC3_11") (pintype "bidirectional"))
    )
    (net (code "92") (name "unconnected-(U$3-PC5-Pad25)") (class "Default")
      (node (ref "U$3") (pin "25") (pinfunction "PC5_25") (pintype "bidirectional"))
    )
    (net (code "93") (name "unconnected-(U$3-PC6{slash}I2S2_MCK-Pad37)") (class "Default")
      (node (ref "U$3") (pin "37") (pinfunction "PC6/I2S2_MCK_37") (pintype "bidirectional"))
    )
    (net (code "94") (name "unconnected-(U$3-PC7-Pad38)") (class "Default")
      (node (ref "U$3") (pin "38") (pinfunction "PC7_38") (pintype "bidirectional"))
    )
    (net (code "95") (name "unconnected-(U$3-PC8{slash}SDIO_D0-Pad39)") (class "Default")
      (node (ref "U$3") (pin "39") (pinfunction "PC8/SDIO_D0_39") (pintype "bidirectional"))
    )
    (net (code "96") (name "unconnected-(U$3-PC9{slash}SDIO_D1-Pad40)") (class "Default")
      (node (ref "U$3") (pin "40") (pinfunction "PC9/SDIO_D1_40") (pintype "bidirectional"))
    )
    (net (code "97") (name "unconnected-(U$3-PC13-Pad2)") (class "Default")
      (node (ref "U$3") (pin "2") (pinfunction "PC13_2") (pintype "bidirectional"))
    )
    (net (code "98") (name "unconnected-(U$3-PC14-Pad3)") (class "Default")
      (node (ref "U$3") (pin "3") (pinfunction "PC14_3") (pintype "bidirectional"))
    )
    (net (code "99") (name "unconnected-(U$3-PC15-Pad4)") (class "Default")
      (node (ref "U$3") (pin "4") (pinfunction "PC15_4") (pintype "bidirectional"))
    )
    (net (code "100") (name "unconnected-(U$3-PD2{slash}SDIO_CMD-Pad54)") (class "Default")
      (node (ref "U$3") (pin "54") (pinfunction "PD2/SDIO_CMD_54") (pintype "bidirectional"))
    )
    (net (code "101") (name "unconnected-(U$3-PH1-Pad6)") (class "Default")
      (node (ref "U$3") (pin "6") (pinfunction "PH1_6") (pintype "bidirectional"))
    )
  )
)
